# LEDLightSticks_V2--02--Power_Dist_PCB_v3.net
KiCad netlist of a schematic drawn in EAGLE
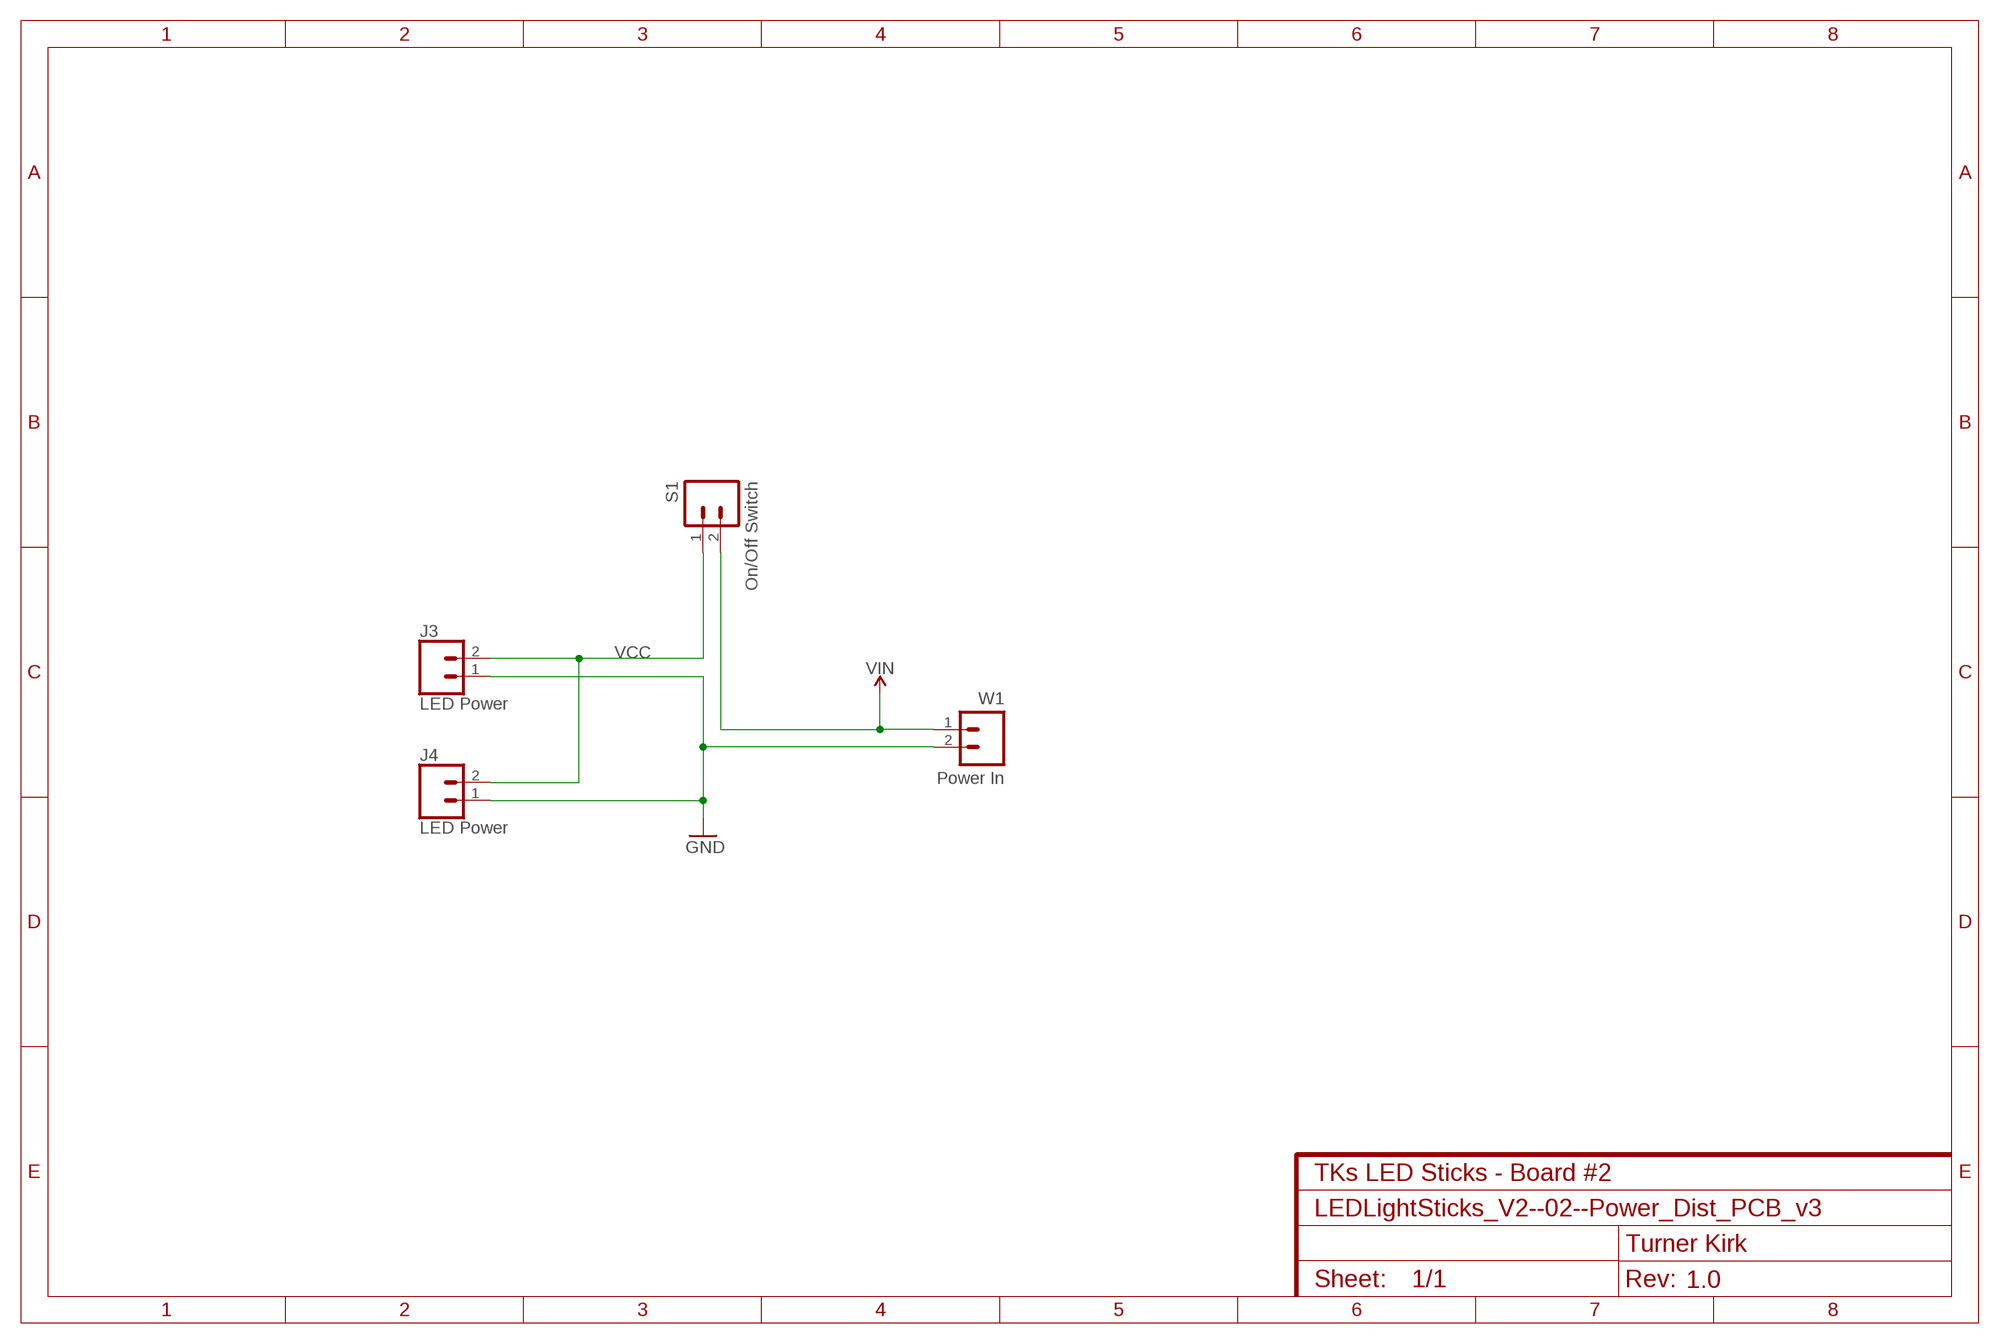
[diagram p0: schematic, sheet 1]

(export (version "E")
  (design (tool "Eeschema 10.0.6"))
  (components
    (comp (ref "J3")
      (value "LED Power")
      (footprint "eagle-import:JST-2-PTH-XH-RA")
      (libsource (lib "eagle-import") (part "CONN_02JST-2.5-PTH-XH-RA"))
    )
    (comp (ref "J4")
      (value "LED Power")
      (footprint "eagle-import:JST-2-PTH-XH-RA")
      (libsource (lib "eagle-import") (part "CONN_02JST-2.5-PTH-XH-RA"))
    )
    (comp (ref "S1")
      (value "On/Off Switch")
      (footprint "eagle-import:1X02_1.5MM")
      (libsource (lib "eagle-import") (part "CONN_02PTH-1.5MM_DRILL"))
    )
    (comp (ref "W1")
      (value "Power In")
      (footprint "eagle-import:1X02_1.5MM")
      (libsource (lib "eagle-import") (part "CONN_02PTH-1.5MM_DRILL"))
    )
  )
  (nets
    (net (code "1") (name "/VCC") (class "Default")
      (node (ref "J3") (pin "2") (pinfunction "2_2") (pintype "passive"))
      (node (ref "J4") (pin "2") (pinfunction "2_2") (pintype "passive"))
      (node (ref "S1") (pin "1") (pinfunction "1_1") (pintype "passive"))
    )
    (net (code "2") (name "GND") (class "Default")
      (node (ref "J3") (pin "1") (pinfunction "1_1") (pintype "passive"))
      (node (ref "J4") (pin "1") (pinfunction "1_1") (pintype "passive"))
      (node (ref "W1") (pin "2") (pinfunction "2_2") (pintype "passive"))
    )
    (net (code "3") (name "VIN") (class "Default")
      (node (ref "S1") (pin "2") (pinfunction "2_2") (pintype "passive"))
      (node (ref "W1") (pin "1") (pinfunction "1_1") (pintype "passive"))
    )
  )
)
